# design.net
KiCad netlist of a schematic drawn in EasyEDA Pro
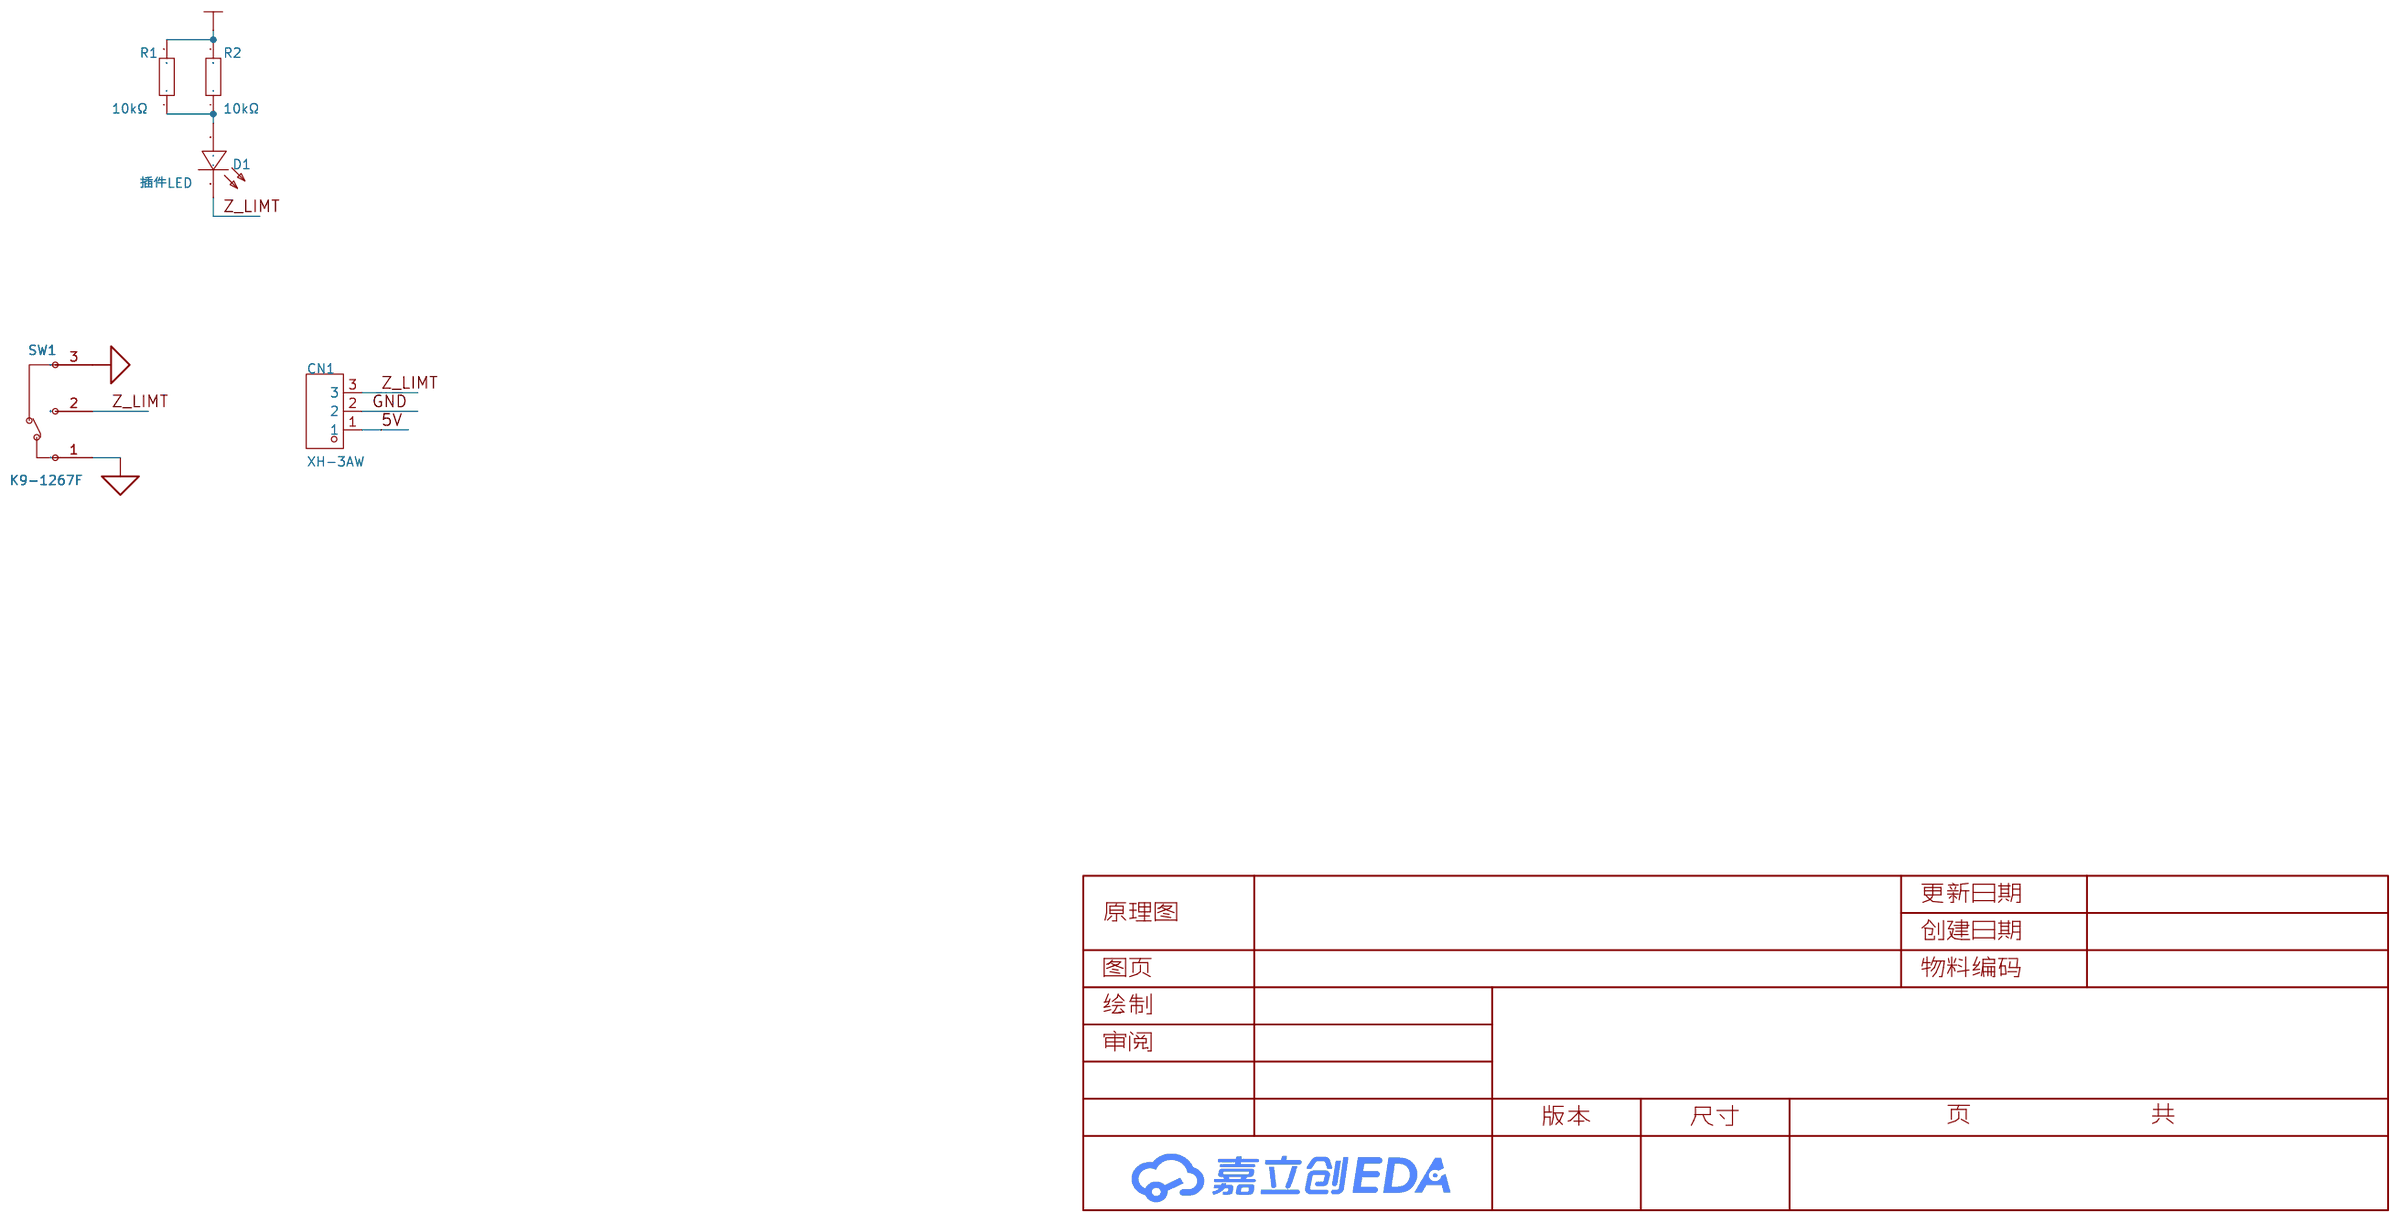
[diagram p0: 主控MCU]
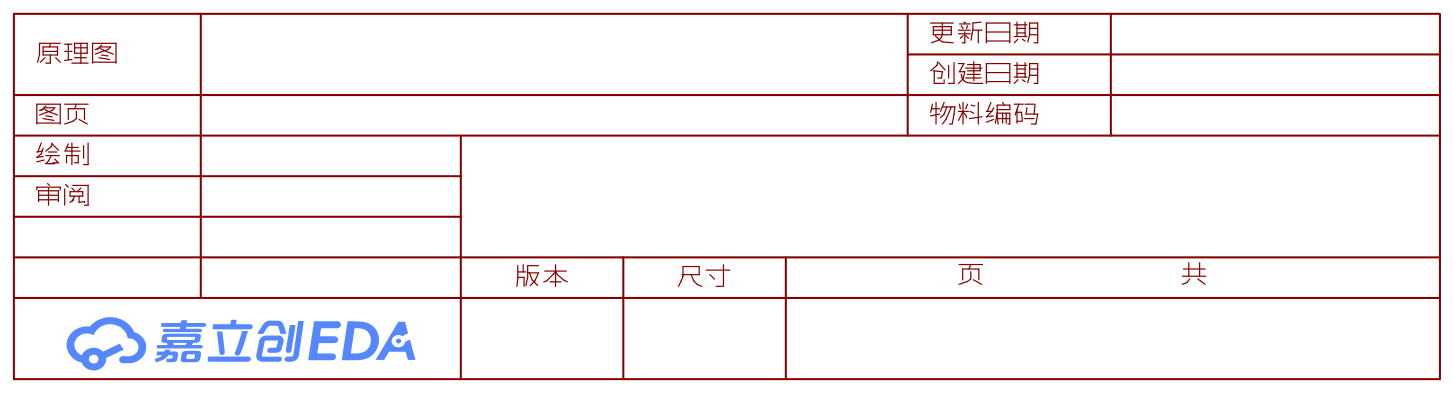
[diagram p1: 电源及控制]

(export (version "E")
  (design (tool "Eeschema 10.0.6"))
  (components
    (comp (ref "CN1")
      (value "XH-3AW")
      (footprint "easyedapro:CONN-TH_3P-P2.50_XH-3A")
      (description "参考系列:XH;间距:2.5mm;插针结构:1x3P;排数:1;每排PIN数:3;行距:-;安装方式:-;触头材质:-;")
      (fields (field (name "Manufacturer") "BOOMELE(博穆精密)"))
      (libsource (lib "easyedapro") (part "XH-3AW_C18428"))
    )
    (comp (ref "D1")
      (value "插件LED")
      (footprint "easyedapro:LED-TH_BD3.8-P2.54-FD")
      (description "发光颜色:红灯;")
      (fields (field (name "Manufacturer") "EVERLIGHT(台湾亿光)"))
      (libsource (lib "easyedapro") (part "204-10SURC/S530-A3-L"))
    )
    (comp (ref "R1")
      (value "10kΩ")
      (footprint "easyedapro:R0805")
      (description "电阻类型:厚膜电阻;阻值:680kΩ;精度:±1%;功率:125mW;温度系数:±100ppm/°C;最大工作电压:150V;工作温度范围:-55°C~+155°C;")
      (fields
        (field (name "Manufacturer Part") "0805W8F6803T5E")
        (field (name "Manufacturer") "UNI-ROYAL(厚声)")
      )
      (libsource (lib "easyedapro") (part "0805W8F6803T5E"))
    )
    (comp (ref "R2")
      (value "10kΩ")
      (footprint "easyedapro:R0805")
      (description "电阻类型:厚膜电阻;阻值:680kΩ;精度:±1%;功率:125mW;温度系数:±100ppm/°C;最大工作电压:150V;工作温度范围:-55°C~+155°C;")
      (fields
        (field (name "Manufacturer Part") "0805W8F6803T5E")
        (field (name "Manufacturer") "UNI-ROYAL(厚声)")
      )
      (libsource (lib "easyedapro") (part "0805W8F6803T5E"))
    )
    (comp (ref "SW1")
      (value "K9-1267F")
      (footprint "easyedapro:SW-TH_K9-1267F")
      (fields (field (name "Manufacturer") "韩国韩荣"))
      (libsource (lib "easyedapro") (part "K9-1267F"))
    )
  )
  (nets
    (net (code "1") (name "5V") (class "Default")
      (node (ref "CN1") (pin "1") (pinfunction "1_1") (pintype "input"))
      (node (ref "R1") (pin "2") (pinfunction "2_2") (pintype "input"))
      (node (ref "R2") (pin "2") (pinfunction "2_2") (pintype "input"))
    )
    (net (code "2") (name "GND") (class "Default")
      (node (ref "CN1") (pin "2") (pinfunction "2_2") (pintype "input"))
      (node (ref "SW1") (pin "1") (pinfunction "C_1") (pintype "input"))
      (node (ref "SW1") (pin "3") (pinfunction "NC_3") (pintype "input"))
    )
    (net (code "3") (name "Net-(D1-A)") (class "Default")
      (node (ref "D1") (pin "1") (pinfunction "A_1") (pintype "input"))
      (node (ref "R1") (pin "1") (pinfunction "1_1") (pintype "input"))
      (node (ref "R2") (pin "1") (pinfunction "1_1") (pintype "input"))
    )
    (net (code "4") (name "Z_LIMT") (class "Default")
      (node (ref "CN1") (pin "3") (pinfunction "3_3") (pintype "input"))
      (node (ref "D1") (pin "2") (pinfunction "K_2") (pintype "input"))
      (node (ref "SW1") (pin "2") (pinfunction "NO_2") (pintype "input"))
    )
  )
)
